# CANShield.net
KiCad netlist of a schematic drawn in Altium Designer
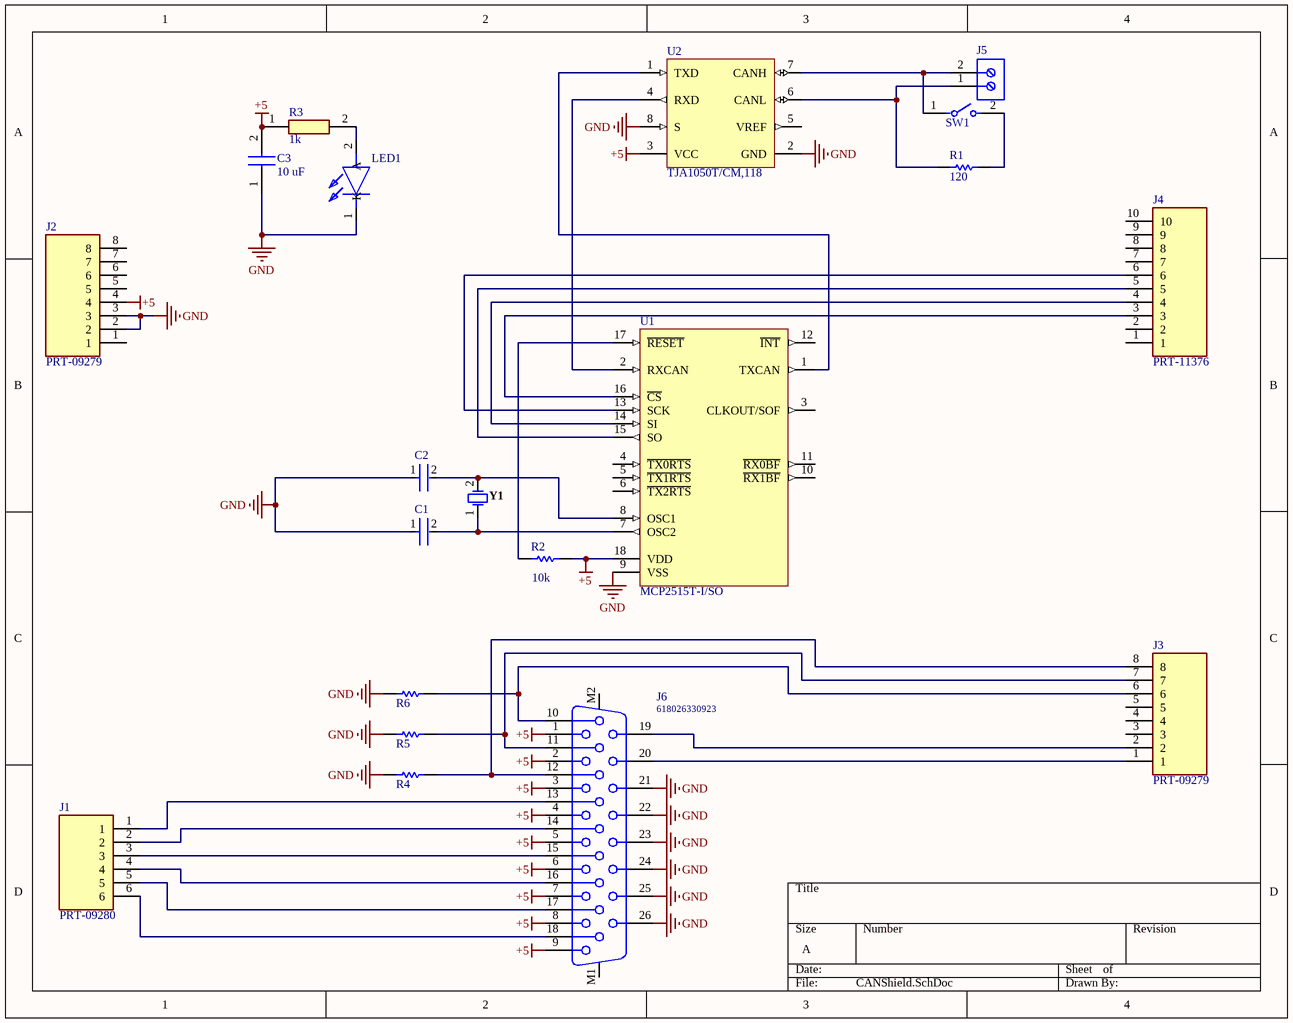
[diagram p0: CANShield.SchDoc]

(export (version "E")
  (design (tool "Eeschema 10.0.6"))
  (components
    (comp (ref "C1")
      (value "C0402C220J8HACTU")
      (footprint "FP-C0402-BB-MFG")
      (description "C0402 22 pF X8R 5.00% 10 V")
      (fields (field (name "TOLERANCE") "0.05") (field (name "MANUFACTURER") "Kemet"))
      (libsource (lib "Altium Content Vault") (part "b4654b650e69147ec39a6b967a45e02"))
    )
    (comp (ref "C2")
      (value "C0402C220J8HACTU")
      (footprint "FP-C0402-BB-MFG")
      (description "C0402 22 pF X8R 5.00% 10 V")
      (fields (field (name "TOLERANCE") "0.05") (field (name "MANUFACTURER") "Kemet"))
      (libsource (lib "Altium Content Vault") (part "b4654b650e69147ec39a6b967a45e02"))
    )
    (comp (ref "C3")
      (value "10 uF")
      (footprint "SamacSys:CAPC1005X55N")
      (description "Capacitor")
      (fields
        (field (name "MANUFACTURER_PART_NUMBER") "0402X106M6R3CT")
        (field (name "MOUSER PART NUMBER") "791-0402X106M6R3CT")
      )
      (libsource (lib "*") (part "0402X106M6R3CT"))
    )
    (comp (ref "J1")
      (value "PRT-09280")
      (footprint "SamacSys:SHDR6W80P0X254_1X6_1579X250X865P")
      (description "Connector")
      (fields (field (name "MOUSER PART NUMBER") "474-PRT-09280"))
      (libsource (lib "*") (part "PRT-09280"))
    )
    (comp (ref "J2")
      (value "PRT-09279")
      (footprint "SamacSys:SHDR8W87P0X254_1X8_2087X250X865P")
      (description "Capacitor")
      (fields (field (name "MOUSER PART NUMBER") "474-PRT-09279"))
      (libsource (lib "*") (part "PRT-09279"))
    )
    (comp (ref "J3")
      (value "PRT-09279")
      (footprint "SamacSys:SHDR8W87P0X254_1X8_2087X250X865P")
      (description "Capacitor")
      (fields (field (name "MOUSER PART NUMBER") "474-PRT-09279"))
      (libsource (lib "") (part "PRT-09279_1"))
    )
    (comp (ref "J4")
      (value "PRT-11376")
      (footprint "SamacSys:SHDR10W107P0X254_1X10_2595X250X865P")
      (description "Capacitor")
      (fields (field (name "MOUSER PART NUMBER") "474-PRT-11376"))
      (libsource (lib "*") (part "PRT-11376"))
    )
    (comp (ref "J5")
      (value "691137710002")
      (footprint "691137710002")
      (description "Series 1377 - 5.00 mm Horizontal Entry with Pressure Clamp WR-TBL, 2 pin")
      (fields (field (name "MANUFACTURER") "Wurth Elektronik") (field (name "PUBLISHER") "WurthElektronik"))
      (libsource (lib "Altium Content Vault") (part "WE-CN-1P-F-TB2"))
    )
    (comp (ref "J6")
      (value "618026330923")
      (footprint "618026330923")
      (description "Female High Density PCB Connector with Hex Screw WR-DSUB, Angled, 26 pins")
      (fields (field (name "MANUFACTURER") "Wurth Elektronik") (field (name "PUBLISHER") "WurthElektronik"))
      (libsource (lib "Altium Content Vault") (part "WE-CN-3S-2F-D26"))
    )
    (comp (ref "LED1")
      (value "150060RS55040")
      (footprint "SamacSys:150060RS55040")
      (description "LED")
      (fields (field (name "MOUSER PART NUMBER") "710-150060RS55040"))
      (libsource (lib "*") (part "150060RS55040"))
    )
    (comp (ref "R1")
      (value "120")
      (footprint "RESC3216X60X45LL10T20")
      (fields (field (name "PART NUMBER") "CRCW1206120RFKEA") (field (name "MANUFACTURER") "Vishay Dale"))
      (libsource (lib "Altium Content Vault") (part "RES"))
    )
    (comp (ref "R2")
      (value "CRCW040210K0FKED")
      (footprint "RESC1005X40X25NL05T05")
      (fields (field (name "MANUFACTURER") "Vishay Dale"))
      (libsource (lib "Altium Content Vault") (part "RES"))
    )
    (comp (ref "R3")
      (value "1k")
      (footprint "SamacSys:RESC2013X55N")
      (description "Resistor")
      (fields
        (field (name "MANUFACTURER_PART_NUMBER") "RGA2012P-102-B-T1")
        (field (name "MOUSER PART NUMBER") "754-RGA2012P-102BT1")
      )
      (libsource (lib "*") (part "RGA2012P-102-B-T1"))
    )
    (comp (ref "R4")
      (value "CRCW040210K0FKED")
      (footprint "RESC1005X40X25NL05T05")
      (fields (field (name "MANUFACTURER") "Vishay Dale"))
      (libsource (lib "Altium Content Vault") (part "RES"))
    )
    (comp (ref "R5")
      (value "CRCW040210K0FKED")
      (footprint "RESC1005X40X25NL05T05")
      (fields (field (name "MANUFACTURER") "Vishay Dale"))
      (libsource (lib "Altium Content Vault") (part "RES"))
    )
    (comp (ref "R6")
      (value "CRCW040210K0FKED")
      (footprint "RESC1005X40X25NL05T05")
      (fields (field (name "MANUFACTURER") "Vishay Dale"))
      (libsource (lib "Altium Content Vault") (part "RES"))
    )
    (comp (ref "SW1")
      (value "5161390-1")
      (footprint "FP-5161390-1-MFG")
      (description "Switch DIP OFF ON SPST 1 Top Slide 25A 50VDC PC Pins 2.54mm Thru-Hole Box/Carton")
      (fields
        (field (name "MANUFACTURER") "TE")
        (field (name "OCTOPART") "https://octopart.com/5161390-1-te+connectivity-46507634")
      )
      (libsource (lib "Altium Content Vault") (part "bb27bde45df87f1f469753f287ef5ae"))
    )
    (comp (ref "U1")
      (value "MCP2515T-I/SO")
      (footprint "SOIC-SO18_N")
      (description "Stand-Alone CAN Controller With SPI Interface, 18-Pin SOIC, Industrial Temperature, Tape and Reel")
      (libsource (lib "Altium Content Vault") (part "COM-CAN-MCP2515-18"))
    )
    (comp (ref "U2")
      (value "TJA1050T/CM,118")
      (footprint "NXP-SOT96-1_M")
      (fields (field (name "MANUFACTURER") "NXP Semiconductors"))
      (libsource (lib "Altium Content Vault") (part "NXP-TJA1050-8"))
    )
    (comp (ref "Y1")
      (value "FOXSDLF/080-20")
      (footprint "FOX-HC49SDLF_V")
      (description "Resistance Weld Crystal, 8 MHz, +/- 30 ppm, -20 to 70 degC, 2-Pin SMD, RoHS, Tape and Reel")
      (fields (field (name "MANUFACTURER") "FOX Electronics") (field (name "TOLERANCE") "50ppm"))
      (libsource (lib "Altium Content Vault") (part "XTAL-1-2-2"))
    )
  )
  (nets
    (net (code "1") (name "+5") (class "Default")
      (node (ref "C3") (pin "2") (pinfunction "2_2") (pintype "passive"))
      (node (ref "J2") (pin "4") (pinfunction "4_4") (pintype "passive"))
      (node (ref "J6") (pin "1") (pinfunction "1_1") (pintype "passive"))
      (node (ref "J6") (pin "2") (pinfunction "2_2") (pintype "passive"))
      (node (ref "J6") (pin "3") (pinfunction "3_3") (pintype "passive"))
      (node (ref "J6") (pin "4") (pinfunction "4_4") (pintype "passive"))
      (node (ref "J6") (pin "5") (pinfunction "5_5") (pintype "passive"))
      (node (ref "J6") (pin "6") (pinfunction "6_6") (pintype "passive"))
      (node (ref "J6") (pin "7") (pinfunction "7_7") (pintype "passive"))
      (node (ref "J6") (pin "8") (pinfunction "8_8") (pintype "passive"))
      (node (ref "J6") (pin "9") (pinfunction "9_9") (pintype "passive"))
      (node (ref "R2") (pin "2") (pinfunction "2_2") (pintype "passive"))
      (node (ref "R3") (pin "1") (pinfunction "1_1") (pintype "passive"))
      (node (ref "U1") (pin "18") (pinfunction "VDD_18") (pintype "power_in"))
      (node (ref "U2") (pin "3") (pinfunction "VCC_3") (pintype "power_in"))
    )
    (net (code "2") (name "GND") (class "Default")
      (node (ref "C1") (pin "1") (pinfunction "1_1") (pintype "passive"))
      (node (ref "C2") (pin "1") (pinfunction "1_1") (pintype "passive"))
      (node (ref "C3") (pin "1") (pinfunction "1_1") (pintype "passive"))
      (node (ref "J2") (pin "2") (pinfunction "2_2") (pintype "passive"))
      (node (ref "J2") (pin "3") (pinfunction "3_3") (pintype "passive"))
      (node (ref "J6") (pin "21") (pinfunction "21_21") (pintype "passive"))
      (node (ref "J6") (pin "22") (pinfunction "22_22") (pintype "passive"))
      (node (ref "J6") (pin "23") (pinfunction "23_23") (pintype "passive"))
      (node (ref "J6") (pin "24") (pinfunction "24_24") (pintype "passive"))
      (node (ref "J6") (pin "25") (pinfunction "25_25") (pintype "passive"))
      (node (ref "J6") (pin "26") (pinfunction "26_26") (pintype "passive"))
      (node (ref "LED1") (pin "1") (pinfunction "K_1") (pintype "passive"))
      (node (ref "R4") (pin "1") (pinfunction "1_1") (pintype "passive"))
      (node (ref "R5") (pin "1") (pinfunction "1_1") (pintype "passive"))
      (node (ref "R6") (pin "1") (pinfunction "1_1") (pintype "passive"))
      (node (ref "U1") (pin "9") (pinfunction "VSS_9") (pintype "power_in"))
      (node (ref "U2") (pin "2") (pinfunction "GND_2") (pintype "power_in"))
      (node (ref "U2") (pin "8") (pinfunction "S_8") (pintype "input"))
    )
    (net (code "3") (name "Net-(J1-Pad1)") (class "Default")
      (node (ref "J1") (pin "1") (pinfunction "1_1") (pintype "passive"))
      (node (ref "J6") (pin "13") (pinfunction "13_13") (pintype "passive"))
    )
    (net (code "4") (name "Net-(J1-Pad2)") (class "Default")
      (node (ref "J1") (pin "2") (pinfunction "2_2") (pintype "passive"))
      (node (ref "J6") (pin "14") (pinfunction "14_14") (pintype "passive"))
    )
    (net (code "5") (name "Net-(J1-Pad3)") (class "Default")
      (node (ref "J1") (pin "3") (pinfunction "3_3") (pintype "passive"))
      (node (ref "J6") (pin "15") (pinfunction "15_15") (pintype "passive"))
    )
    (net (code "6") (name "Net-(J1-Pad4)") (class "Default")
      (node (ref "J1") (pin "4") (pinfunction "4_4") (pintype "passive"))
      (node (ref "J6") (pin "16") (pinfunction "16_16") (pintype "passive"))
    )
    (net (code "7") (name "Net-(J1-Pad5)") (class "Default")
      (node (ref "J1") (pin "5") (pinfunction "5_5") (pintype "passive"))
      (node (ref "J6") (pin "17") (pinfunction "17_17") (pintype "passive"))
    )
    (net (code "8") (name "Net-(J1-Pad6)") (class "Default")
      (node (ref "J1") (pin "6") (pinfunction "6_6") (pintype "passive"))
      (node (ref "J6") (pin "18") (pinfunction "18_18") (pintype "passive"))
    )
    (net (code "9") (name "Net-(J3-Pad1)") (class "Default")
      (node (ref "J3") (pin "1") (pinfunction "1_1") (pintype "passive"))
      (node (ref "J6") (pin "20") (pinfunction "20_20") (pintype "passive"))
    )
    (net (code "10") (name "Net-(J3-Pad2)") (class "Default")
      (node (ref "J3") (pin "2") (pinfunction "2_2") (pintype "passive"))
      (node (ref "J6") (pin "19") (pinfunction "19_19") (pintype "passive"))
    )
    (net (code "11") (name "Net-(J3-Pad6)") (class "Default")
      (node (ref "J3") (pin "6") (pinfunction "6_6") (pintype "passive"))
      (node (ref "J6") (pin "10") (pinfunction "10_10") (pintype "passive"))
      (node (ref "R6") (pin "2") (pinfunction "2_2") (pintype "passive"))
    )
    (net (code "12") (name "Net-(J3-Pad7)") (class "Default")
      (node (ref "J3") (pin "7") (pinfunction "7_7") (pintype "passive"))
      (node (ref "J6") (pin "11") (pinfunction "11_11") (pintype "passive"))
      (node (ref "R5") (pin "2") (pinfunction "2_2") (pintype "passive"))
    )
    (net (code "13") (name "Net-(J3-Pad8)") (class "Default")
      (node (ref "J3") (pin "8") (pinfunction "8_8") (pintype "passive"))
      (node (ref "J6") (pin "12") (pinfunction "12_12") (pintype "passive"))
      (node (ref "R4") (pin "2") (pinfunction "2_2") (pintype "passive"))
    )
    (net (code "14") (name "Net-(LED1-A)") (class "Default")
      (node (ref "LED1") (pin "2") (pinfunction "A_2") (pintype "passive"))
      (node (ref "R3") (pin "2") (pinfunction "2_2") (pintype "passive"))
    )
    (net (code "15") (name "Net-(R1-Pad1)") (class "Default")
      (node (ref "R1") (pin "1") (pinfunction "1_1") (pintype "passive"))
      (node (ref "SW1") (pin "2") (pinfunction "2_2") (pintype "passive"))
    )
    (net (code "16") (name "Net-(U1-OSC1)") (class "Default")
      (node (ref "C2") (pin "2") (pinfunction "2_2") (pintype "passive"))
      (node (ref "U1") (pin "8") (pinfunction "OSC1_8") (pintype "input"))
      (node (ref "Y1") (pin "2") (pinfunction "2_2") (pintype "passive"))
    )
    (net (code "17") (name "Net-(U1-OSC2)") (class "Default")
      (node (ref "C1") (pin "2") (pinfunction "2_2") (pintype "passive"))
      (node (ref "U1") (pin "7") (pinfunction "OSC2_7") (pintype "output"))
      (node (ref "Y1") (pin "1") (pinfunction "1_1") (pintype "passive"))
    )
    (net (code "18") (name "Net-(U1-RXCAN)") (class "Default")
      (node (ref "U1") (pin "2") (pinfunction "RXCAN_2") (pintype "input"))
      (node (ref "U2") (pin "4") (pinfunction "RXD_4") (pintype "output"))
    )
    (net (code "19") (name "Net-(U1-SCK)") (class "Default")
      (node (ref "J4") (pin "6") (pinfunction "6_6") (pintype "passive"))
      (node (ref "U1") (pin "13") (pinfunction "SCK_13") (pintype "input"))
    )
    (net (code "20") (name "Net-(U1-SI)") (class "Default")
      (node (ref "J4") (pin "4") (pinfunction "4_4") (pintype "passive"))
      (node (ref "U1") (pin "14") (pinfunction "SI_14") (pintype "input"))
    )
    (net (code "21") (name "Net-(U1-SO)") (class "Default")
      (node (ref "J4") (pin "5") (pinfunction "5_5") (pintype "passive"))
      (node (ref "U1") (pin "15") (pinfunction "SO_15") (pintype "output"))
    )
    (net (code "22") (name "Net-(U1-TXCAN)") (class "Default")
      (node (ref "U1") (pin "1") (pinfunction "TXCAN_1") (pintype "output"))
      (node (ref "U2") (pin "1") (pinfunction "TXD_1") (pintype "input"))
    )
    (net (code "23") (name "Net-(U1-~{CS})") (class "Default")
      (node (ref "J4") (pin "3") (pinfunction "3_3") (pintype "passive"))
      (node (ref "U1") (pin "16") (pinfunction "~{CS}_16") (pintype "input"))
    )
    (net (code "24") (name "Net-(U1-~{RESET})") (class "Default")
      (node (ref "R2") (pin "1") (pinfunction "1_1") (pintype "passive"))
      (node (ref "U1") (pin "17") (pinfunction "~{RESET}_17") (pintype "input"))
    )
    (net (code "25") (name "Net-(U2-CANH)") (class "Default")
      (node (ref "J5") (pin "2") (pinfunction "2_2") (pintype "passive"))
      (node (ref "SW1") (pin "1") (pinfunction "1_1") (pintype "passive"))
      (node (ref "U2") (pin "7") (pinfunction "CANH_7") (pintype "bidirectional"))
    )
    (net (code "26") (name "Net-(U2-CANL)") (class "Default")
      (node (ref "J5") (pin "1") (pinfunction "1_1") (pintype "passive"))
      (node (ref "R1") (pin "2") (pinfunction "2_2") (pintype "passive"))
      (node (ref "U2") (pin "6") (pinfunction "CANL_6") (pintype "bidirectional"))
    )
    (net (code "27") (name "unconnected-(J2-Pad1)") (class "Default")
      (node (ref "J2") (pin "1") (pinfunction "1_1") (pintype "passive"))
    )
    (net (code "28") (name "unconnected-(J2-Pad5)") (class "Default")
      (node (ref "J2") (pin "5") (pinfunction "5_5") (pintype "passive"))
    )
    (net (code "29") (name "unconnected-(J2-Pad6)") (class "Default")
      (node (ref "J2") (pin "6") (pinfunction "6_6") (pintype "passive"))
    )
    (net (code "30") (name "unconnected-(J2-Pad7)") (class "Default")
      (node (ref "J2") (pin "7") (pinfunction "7_7") (pintype "passive"))
    )
    (net (code "31") (name "unconnected-(J2-Pad8)") (class "Default")
      (node (ref "J2") (pin "8") (pinfunction "8_8") (pintype "passive"))
    )
    (net (code "32") (name "unconnected-(J3-Pad3)") (class "Default")
      (node (ref "J3") (pin "3") (pinfunction "3_3") (pintype "passive"))
    )
    (net (code "33") (name "unconnected-(J3-Pad4)") (class "Default")
      (node (ref "J3") (pin "4") (pinfunction "4_4") (pintype "passive"))
    )
    (net (code "34") (name "unconnected-(J3-Pad5)") (class "Default")
      (node (ref "J3") (pin "5") (pinfunction "5_5") (pintype "passive"))
    )
    (net (code "35") (name "unconnected-(J4-Pad1)") (class "Default")
      (node (ref "J4") (pin "1") (pinfunction "1_1") (pintype "passive"))
    )
    (net (code "36") (name "unconnected-(J4-Pad2)") (class "Default")
      (node (ref "J4") (pin "2") (pinfunction "2_2") (pintype "passive"))
    )
    (net (code "37") (name "unconnected-(J4-Pad7)") (class "Default")
      (node (ref "J4") (pin "7") (pinfunction "7_7") (pintype "passive"))
    )
    (net (code "38") (name "unconnected-(J4-Pad8)") (class "Default")
      (node (ref "J4") (pin "8") (pinfunction "8_8") (pintype "passive"))
    )
    (net (code "39") (name "unconnected-(J4-Pad9)") (class "Default")
      (node (ref "J4") (pin "9") (pinfunction "9_9") (pintype "passive"))
    )
    (net (code "40") (name "unconnected-(J4-Pad10)") (class "Default")
      (node (ref "J4") (pin "10") (pinfunction "10_10") (pintype "passive"))
    )
    (net (code "41") (name "unconnected-(J6-PadM1)") (class "Default")
      (node (ref "J6") (pin "M1") (pinfunction "M1_M1") (pintype "passive"))
    )
    (net (code "42") (name "unconnected-(J6-PadM2)") (class "Default")
      (node (ref "J6") (pin "M2") (pinfunction "M2_M2") (pintype "passive"))
    )
    (net (code "43") (name "unconnected-(U1-CLKOUT{slash}SOF-Pad3)") (class "Default")
      (node (ref "U1") (pin "3") (pinfunction "CLKOUT/SOF_3") (pintype "output"))
    )
    (net (code "44") (name "unconnected-(U1-~{INT}-Pad12)") (class "Default")
      (node (ref "U1") (pin "12") (pinfunction "~{INT}_12") (pintype "output"))
    )
    (net (code "45") (name "unconnected-(U1-~{RX0BF}-Pad11)") (class "Default")
      (node (ref "U1") (pin "11") (pinfunction "~{RX0BF}_11") (pintype "output"))
    )
    (net (code "46") (name "unconnected-(U1-~{RX1BF}-Pad10)") (class "Default")
      (node (ref "U1") (pin "10") (pinfunction "~{RX1BF}_10") (pintype "output"))
    )
    (net (code "47") (name "unconnected-(U1-~{TX0RTS}-Pad4)") (class "Default")
      (node (ref "U1") (pin "4") (pinfunction "~{TX0RTS}_4") (pintype "input"))
    )
    (net (code "48") (name "unconnected-(U1-~{TX1RTS}-Pad5)") (class "Default")
      (node (ref "U1") (pin "5") (pinfunction "~{TX1RTS}_5") (pintype "input"))
    )
    (net (code "49") (name "unconnected-(U1-~{TX2RTS}-Pad6)") (class "Default")
      (node (ref "U1") (pin "6") (pinfunction "~{TX2RTS}_6") (pintype "input"))
    )
    (net (code "50") (name "unconnected-(U2-VREF-Pad5)") (class "Default")
      (node (ref "U2") (pin "5") (pinfunction "VREF_5") (pintype "output"))
    )
  )
)
